# powerSupply.net
KiCad netlist of a schematic drawn in Altium Designer
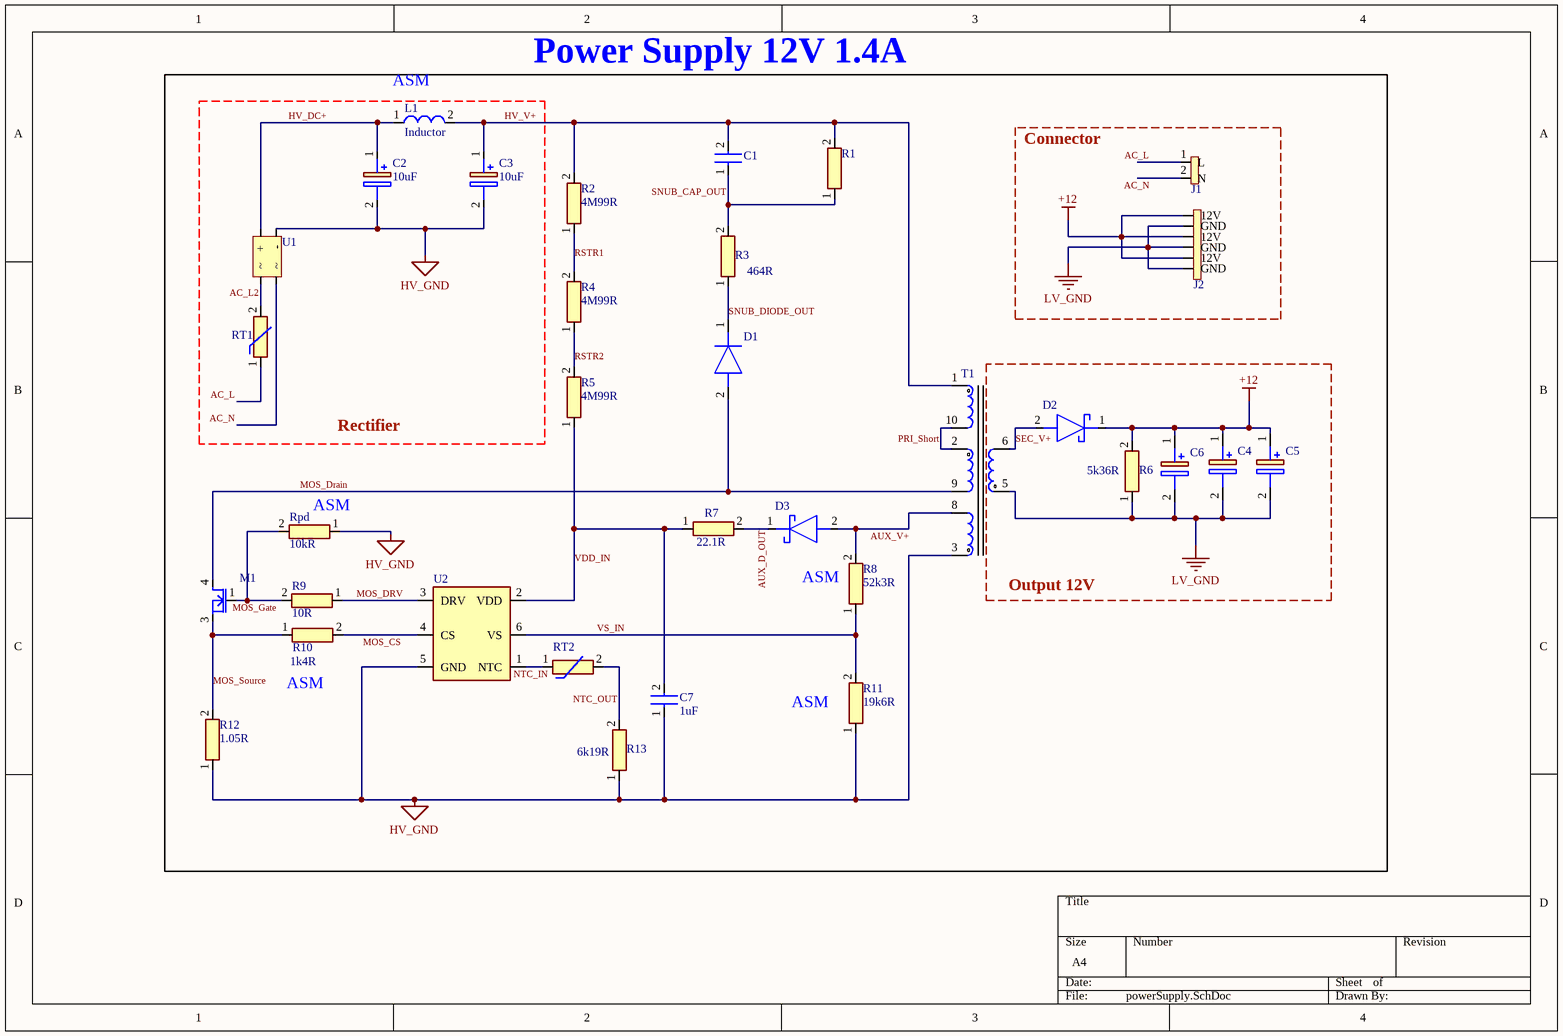
[diagram p0: powerSupply.SchDoc]

(export (version "E")
  (design (tool "Eeschema 10.0.6"))
  (components
    (comp (ref "C1")
      (value "0805C")
      (footprint "PcbLib1:0805C")
      (description "10nF")
      (libsource (lib "Schlib1") (part "0805C"))
    )
    (comp (ref "C2")
      (value "10uF")
      (footprint "PcbLib1:10uF")
      (description "Alum. Electrolytic Cap 10µF 400V 10mm Radial WCAP-AT1H; Lifetime 10000h +105°C")
      (fields
        (field (name "MANUFACTURER") "Wurth Electronics")
        (field (name "MANUFACTURER PART NUMBER") "860241375002")
      )
      (libsource (lib "Schlib1") (part "10uF(Cin)"))
    )
    (comp (ref "C3")
      (value "10uF")
      (footprint "PcbLib1:10uF")
      (description "Alum. Electrolytic Cap 10µF 400V 10mm Radial WCAP-AT1H; Lifetime 10000h +105°C")
      (fields
        (field (name "MANUFACTURER") "Wurth Electronics")
        (field (name "MANUFACTURER PART NUMBER") "860241375002")
      )
      (libsource (lib "Schlib1") (part "10uF(Cin)"))
    )
    (comp (ref "C4")
      (value "16SVPG270MX")
      (footprint "PcbLib1:Cout")
      (description "Capacitor Polarised")
      (fields (field (name "MOUSER PART NUMBER") "667-16SVPG270MX"))
      (libsource (lib "Schlib1") (part "Cout"))
    )
    (comp (ref "C5")
      (value "16SVPG270MX")
      (footprint "PcbLib1:Cout")
      (description "Capacitor Polarised")
      (fields (field (name "MOUSER PART NUMBER") "667-16SVPG270MX"))
      (libsource (lib "Schlib1") (part "Cout"))
    )
    (comp (ref "C6")
      (value "16SVPG270MX")
      (footprint "PcbLib1:Cout")
      (description "Capacitor Polarised")
      (fields (field (name "MOUSER PART NUMBER") "667-16SVPG270MX"))
      (libsource (lib "Schlib1") (part "Cout"))
    )
    (comp (ref "C7")
      (value "1uF")
      (footprint "PcbLib1:1206C")
      (description "Cap Ceramic 1uF 100V X7R 10% SMD 1206 125°C Embossed T/R")
      (fields
        (field (name "MANUFACTURER") "Kyocera AVX")
        (field (name "MANUFACTURER PART NUMBER") "12061C105KAT4A")
      )
      (libsource (lib "Schlib1") (part "1206C"))
    )
    (comp (ref "D1")
      (value "UFS180Je3_TR13")
      (footprint "PcbLib1:UFS180Je3_TR13")
      (description "Diode")
      (fields
        (field (name "MANUFACTURER_PART_NUMBER") "UFS180Je3/TR13")
        (field (name "MOUSER PART NUMBER") "494-UFS180JE3/TR13")
      )
      (libsource (lib "Schlib1") (part "UFS180Je3_TR13"))
    )
    (comp (ref "D2")
      (value "RB058LAM100TR")
      (footprint "PcbLib1:Shottky_Diode")
      (description "Schottky Diode")
      (fields (field (name "MOUSER PART NUMBER") "755-RB058LAM100TR"))
      (libsource (lib "Schlib1") (part "Shottky_Diode"))
    )
    (comp (ref "D3")
      (value "RB058LAM100TR")
      (footprint "PcbLib1:Shottky_Diode")
      (description "Schottky Diode")
      (fields (field (name "MOUSER PART NUMBER") "755-RB058LAM100TR"))
      (libsource (lib "Schlib1") (part "Shottky_Diode"))
    )
    (comp (ref "J1")
      (value "AC(IN)")
      (footprint "PcbLib1:AC(IN)")
      (libsource (lib "Schlib1") (part "AC(IN)"))
    )
    (comp (ref "J2") (value "12V") (footprint "PcbLib1:1x6P") (libsource (lib "Schlib1") (part "Out(12V)")))
    (comp (ref "L1")
      (value "Inductor")
      (footprint "PcbLib1:INDP125125X600N")
      (description "Inductor Power Shielded Wirewound 470uH 10% 1KHz 18Q-Factor Ferrite 0.18A 3.3Ohm DCR T/R")
      (fields
        (field (name "MANUFACTURER") "Bourns")
        (field (name "MANUFACTURER PART NUMBER") "SRR0604-471KL")
      )
      (libsource (lib "Schlib1") (part "470uH(L1)"))
    )
    (comp (ref "M1")
      (value "MOSFET")
      (footprint "PcbLib1:MOSFET")
      (description "Single N-Channel 800 V 900 mOhm 15 nC CoolMOS Power Mosfet - DPAK")
      (fields
        (field (name "MANUFACTURER") "Infineon")
        (field (name "MANUFACTURER PART NUMBER") "IPD80R900P7ATMA1")
      )
      (libsource (lib "Schlib1") (part "MOSFET"))
    )
    (comp (ref "R1")
      (value "3W-Resistor")
      (footprint "PcbLib1:3W-Resistor")
      (description "Resistor")
      (fields
        (field (name "MANUFACTURER_PART_NUMBER") "PR03000206202JAC00")
        (field (name "MOUSER PART NUMBER") "594-5093NW62K00J")
      )
      (libsource (lib "Schlib1") (part "3W-Resistor"))
    )
    (comp (ref "R2") (value "4M99R") (footprint "PcbLib1:0805R") (libsource (lib "Schlib1") (part "0805R")))
    (comp (ref "R3") (value "464R") (footprint "PcbLib1:0402R") (libsource (lib "") (part "0402R_1")))
    (comp (ref "R4") (value "4M99R") (footprint "PcbLib1:0805R") (libsource (lib "Schlib1") (part "0805R")))
    (comp (ref "R5") (value "4M99R") (footprint "PcbLib1:0805R") (libsource (lib "Schlib1") (part "0805R")))
    (comp (ref "R6") (value "5k36R") (footprint "PcbLib1:0402R") (libsource (lib "") (part "0402R_1")))
    (comp (ref "R7") (value "22.1R") (footprint "PcbLib1:0402R") (libsource (lib "Schlib1") (part "0402R")))
    (comp (ref "R8") (value "52k3R") (footprint "PcbLib1:0603R") (libsource (lib "Schlib1") (part "0603R")))
    (comp (ref "R9") (value "10R") (footprint "PcbLib1:0805R") (libsource (lib "") (part "0805R_1")))
    (comp (ref "R10") (value "1k4R") (footprint "PcbLib1:0402R") (libsource (lib "Schlib1") (part "0402R")))
    (comp (ref "R11")
      (value "19k6R")
      (footprint "PcbLib1:0603R")
      (fields (field (name "LCSC PART NO") "C321774"))
      (libsource (lib "Schlib1") (part "0603R"))
    )
    (comp (ref "R12") (value "1.05R") (footprint "PcbLib1:1206R") (libsource (lib "Schlib1") (part "1206R")))
    (comp (ref "R13") (value "6k19R") (footprint "PcbLib1:0402R") (libsource (lib "") (part "0402R_1")))
    (comp (ref "Rpd") (value "10kR") (footprint "PcbLib1:0805R") (libsource (lib "") (part "0805R_1")))
    (comp (ref "RT1")
      (value "Cl-60")
      (footprint "PcbLib1:CL-60")
      (description "CL Series 10 Ohm ± 25 % 5 A Radial Uninsulated Leads Thermistor Disc")
      (fields (field (name "MANUFACTURER") "Amphenol") (field (name "MANUFACTURER PART NUMBER") "CL-60"))
      (libsource (lib "Schlib1") (part "Cl-60"))
    )
    (comp (ref "RT2")
      (value "NTCG104BF683JT1X")
      (footprint "PcbLib1:NTC")
      (description "Thermistor")
      (fields (field (name "MOUSER PART NUMBER") "810-NTCG104BF683JT"))
      (libsource (lib "Schlib1") (part "NTC"))
    )
    (comp (ref "T1")
      (value "750312495")
      (footprint "PcbLib1:750312495")
      (description "Transformer")
      (fields (field (name "MOUSER PART NUMBER") "710-750312495"))
      (libsource (lib "Schlib1") (part "Transformer"))
    )
    (comp (ref "U1")
      (value "CD-MBL206SL")
      (footprint "PcbLib1:CD-MBL210S_1")
      (description "DIO BR VRRM 600V 2A MBLS / Tape & Reel - 13\" reel RoHS Compliant: Yes")
      (fields (field (name "MANUFACTURER") "Bourns"))
      (libsource (lib "Schlib1") (part "Bridge_Rectifier"))
    )
    (comp (ref "U2")
      (value "UCC28701DBVT")
      (footprint "PcbLib1:SOT95P280X145-6N")
      (description "Integrated Circuit")
      (fields (field (name "MOUSER PART NUMBER") "595-UCC28701DBVT"))
      (libsource (lib "Schlib1") (part "Flyback_Controller"))
    )
  )
  (nets
    (net (code "1") (name "+12") (class "Default")
      (node (ref "C4") (pin "1") (pinfunction "+_1") (pintype "passive"))
      (node (ref "C5") (pin "1") (pinfunction "+_1") (pintype "passive"))
      (node (ref "C6") (pin "1") (pinfunction "+_1") (pintype "passive"))
      (node (ref "D2") (pin "1") (pinfunction "K_1") (pintype "passive"))
      (node (ref "J2") (pin "2") (pinfunction "12V_2") (pintype "passive"))
      (node (ref "J2") (pin "4") (pinfunction "12V_4") (pintype "passive"))
      (node (ref "J2") (pin "6") (pinfunction "12V_6") (pintype "passive"))
      (node (ref "R6") (pin "2") (pinfunction "2_2") (pintype "passive"))
    )
    (net (code "2") (name "/AC_L") (class "Default")
      (node (ref "J1") (pin "1") (pinfunction "L_1") (pintype "passive"))
      (node (ref "RT1") (pin "1") (pinfunction "1_1") (pintype "passive"))
    )
    (net (code "3") (name "/AC_L2") (class "Default")
      (node (ref "RT1") (pin "2") (pinfunction "2_2") (pintype "passive"))
      (node (ref "U1") (pin "2") (pinfunction "~_2") (pintype "passive"))
    )
    (net (code "4") (name "/AC_N") (class "Default")
      (node (ref "J1") (pin "2") (pinfunction "N_2") (pintype "passive"))
      (node (ref "U1") (pin "3") (pinfunction "~_3") (pintype "passive"))
    )
    (net (code "5") (name "/AUX_D_OUT") (class "Default")
      (node (ref "D3") (pin "1") (pinfunction "K_1") (pintype "passive"))
      (node (ref "R7") (pin "2") (pinfunction "2_2") (pintype "passive"))
    )
    (net (code "6") (name "/AUX_V+") (class "Default")
      (node (ref "D3") (pin "2") (pinfunction "A_2") (pintype "passive"))
      (node (ref "R8") (pin "2") (pinfunction "2_2") (pintype "passive"))
      (node (ref "T1") (pin "8") (pinfunction "8_8") (pintype "passive"))
    )
    (net (code "7") (name "/HV_DC+") (class "Default")
      (node (ref "C2") (pin "1") (pinfunction "+_1") (pintype "passive"))
      (node (ref "L1") (pin "1") (pinfunction "1_1") (pintype "passive"))
      (node (ref "U1") (pin "1") (pinfunction "+_1") (pintype "passive"))
    )
    (net (code "8") (name "/HV_V+") (class "Default")
      (node (ref "C1") (pin "2") (pinfunction "2_2") (pintype "passive"))
      (node (ref "C3") (pin "1") (pinfunction "+_1") (pintype "passive"))
      (node (ref "L1") (pin "2") (pinfunction "2_2") (pintype "passive"))
      (node (ref "R1") (pin "2") (pinfunction "2_2") (pintype "passive"))
      (node (ref "R2") (pin "2") (pinfunction "2_2") (pintype "passive"))
      (node (ref "T1") (pin "1") (pinfunction "1_1") (pintype "passive"))
    )
    (net (code "9") (name "/MOS_CS") (class "Default")
      (node (ref "R10") (pin "2") (pinfunction "2_2") (pintype "passive"))
      (node (ref "U2") (pin "4") (pinfunction "CS_4") (pintype "passive"))
    )
    (net (code "10") (name "/MOS_DRV") (class "Default")
      (node (ref "R9") (pin "1") (pinfunction "1_1") (pintype "passive"))
      (node (ref "U2") (pin "3") (pinfunction "DRV_3") (pintype "passive"))
    )
    (net (code "11") (name "/MOS_Drain") (class "Default")
      (node (ref "D1") (pin "2") (pinfunction "A_2") (pintype "passive"))
      (node (ref "M1") (pin "4") (pinfunction "D_4") (pintype "passive"))
      (node (ref "T1") (pin "9") (pinfunction "9_9") (pintype "passive"))
    )
    (net (code "12") (name "/MOS_Gate") (class "Default")
      (node (ref "M1") (pin "1") (pinfunction "G_1") (pintype "passive"))
      (node (ref "R9") (pin "2") (pinfunction "2_2") (pintype "passive"))
      (node (ref "Rpd") (pin "2") (pinfunction "2_2") (pintype "passive"))
    )
    (net (code "13") (name "/MOS_Source") (class "Default")
      (node (ref "M1") (pin "3") (pinfunction "S_3") (pintype "passive"))
      (node (ref "R10") (pin "1") (pinfunction "1_1") (pintype "passive"))
      (node (ref "R12") (pin "2") (pinfunction "2_2") (pintype "passive"))
    )
    (net (code "14") (name "/NTC_IN") (class "Default")
      (node (ref "RT2") (pin "1") (pinfunction "1_1") (pintype "passive"))
      (node (ref "U2") (pin "1") (pinfunction "NTC_1") (pintype "passive"))
    )
    (net (code "15") (name "/NTC_OUT") (class "Default")
      (node (ref "R13") (pin "2") (pinfunction "2_2") (pintype "passive"))
      (node (ref "RT2") (pin "2") (pinfunction "2_2") (pintype "passive"))
    )
    (net (code "16") (name "/PRI_Short") (class "Default")
      (node (ref "T1") (pin "10") (pinfunction "10_10") (pintype "passive"))
      (node (ref "T1") (pin "2") (pinfunction "2_2") (pintype "passive"))
    )
    (net (code "17") (name "/RSTR1") (class "Default")
      (node (ref "R2") (pin "1") (pinfunction "1_1") (pintype "passive"))
      (node (ref "R4") (pin "2") (pinfunction "2_2") (pintype "passive"))
    )
    (net (code "18") (name "/RSTR2") (class "Default")
      (node (ref "R4") (pin "1") (pinfunction "1_1") (pintype "passive"))
      (node (ref "R5") (pin "2") (pinfunction "2_2") (pintype "passive"))
    )
    (net (code "19") (name "/SEC_V+") (class "Default")
      (node (ref "D2") (pin "2") (pinfunction "A_2") (pintype "passive"))
      (node (ref "T1") (pin "6") (pinfunction "6_6") (pintype "passive"))
    )
    (net (code "20") (name "/SNUB_CAP_OUT") (class "Default")
      (node (ref "C1") (pin "1") (pinfunction "1_1") (pintype "passive"))
      (node (ref "R1") (pin "1") (pinfunction "1_1") (pintype "passive"))
      (node (ref "R3") (pin "2") (pinfunction "2_2") (pintype "passive"))
    )
    (net (code "21") (name "/SNUB_DIODE_OUT") (class "Default")
      (node (ref "D1") (pin "1") (pinfunction "K_1") (pintype "passive"))
      (node (ref "R3") (pin "1") (pinfunction "1_1") (pintype "passive"))
    )
    (net (code "22") (name "/VDD_IN") (class "Default")
      (node (ref "C7") (pin "2") (pinfunction "2_2") (pintype "passive"))
      (node (ref "R5") (pin "1") (pinfunction "1_1") (pintype "passive"))
      (node (ref "R7") (pin "1") (pinfunction "1_1") (pintype "passive"))
      (node (ref "U2") (pin "2") (pinfunction "VDD_2") (pintype "passive"))
    )
    (net (code "23") (name "/VS_IN") (class "Default")
      (node (ref "R11") (pin "2") (pinfunction "2_2") (pintype "passive"))
      (node (ref "R8") (pin "1") (pinfunction "1_1") (pintype "passive"))
      (node (ref "U2") (pin "6") (pinfunction "VS_6") (pintype "passive"))
    )
    (net (code "24") (name "HV_GND") (class "Default")
      (node (ref "C2") (pin "2") (pinfunction "-_2") (pintype "passive"))
      (node (ref "C3") (pin "2") (pinfunction "-_2") (pintype "passive"))
      (node (ref "C7") (pin "1") (pinfunction "1_1") (pintype "passive"))
      (node (ref "R11") (pin "1") (pinfunction "1_1") (pintype "passive"))
      (node (ref "R12") (pin "1") (pinfunction "1_1") (pintype "passive"))
      (node (ref "R13") (pin "1") (pinfunction "1_1") (pintype "passive"))
      (node (ref "Rpd") (pin "1") (pinfunction "1_1") (pintype "passive"))
      (node (ref "T1") (pin "3") (pinfunction "3_3") (pintype "passive"))
      (node (ref "U1") (pin "4") (pinfunction "-_4") (pintype "passive"))
      (node (ref "U2") (pin "5") (pinfunction "GND_5") (pintype "passive"))
    )
    (net (code "25") (name "LV_GND") (class "Default")
      (node (ref "C4") (pin "2") (pinfunction "-_2") (pintype "passive"))
      (node (ref "C5") (pin "2") (pinfunction "-_2") (pintype "passive"))
      (node (ref "C6") (pin "2") (pinfunction "-_2") (pintype "passive"))
      (node (ref "J2") (pin "1") (pinfunction "GND_1") (pintype "passive"))
      (node (ref "J2") (pin "3") (pinfunction "GND_3") (pintype "passive"))
      (node (ref "J2") (pin "5") (pinfunction "GND_5") (pintype "passive"))
      (node (ref "R6") (pin "1") (pinfunction "1_1") (pintype "passive"))
      (node (ref "T1") (pin "5") (pinfunction "5_5") (pintype "passive"))
    )
  )
)
